# SCH_usbhubby_2024-08-02.net
KiCad netlist of a schematic drawn in EasyEDA
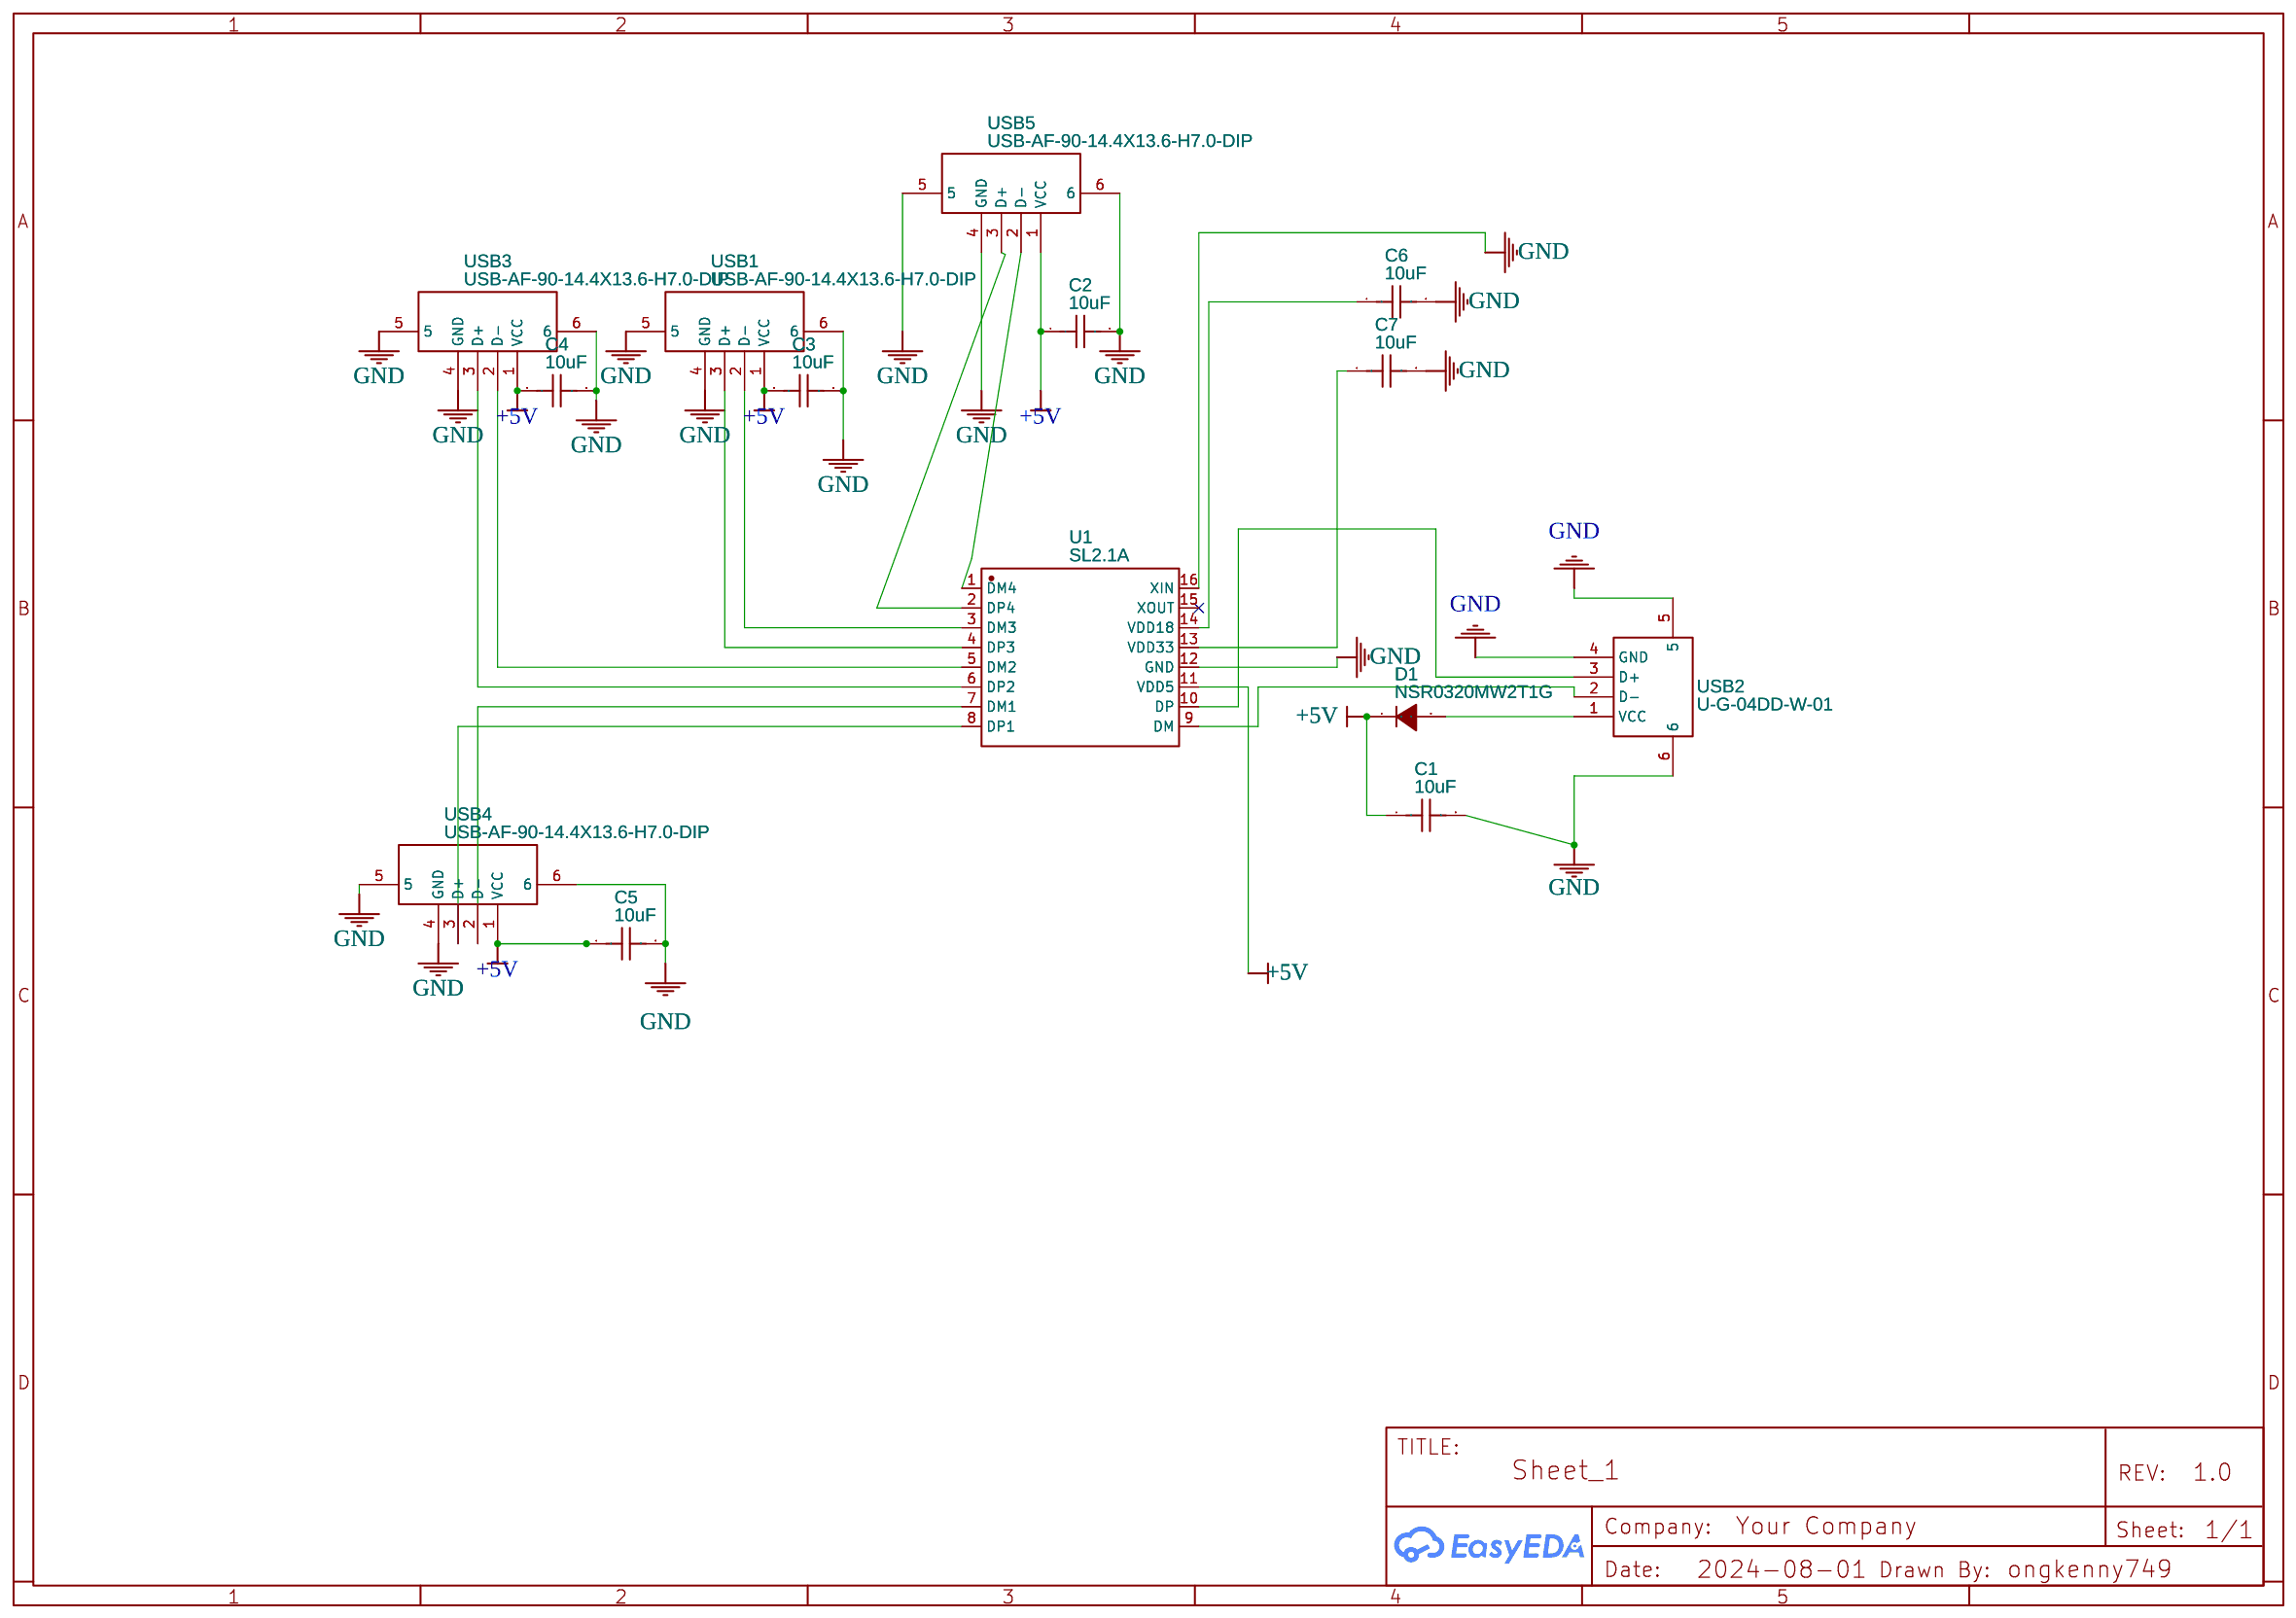
[diagram p0: schematic sheet]

(export (version "E")
  (design (tool "Eeschema 10.0.6"))
  (components
    (comp (ref "C1")
      (value "10uF")
      (fields
        (field (name "Manufacturer Part") "CL10A106KP8NNNC")
        (field (name "Manufacturer") "SAMSUNG(三星)")
      )
      (libsource (lib "") (part "CL10A106KP8NNNC"))
    )
    (comp (ref "C2")
      (value "10uF")
      (fields
        (field (name "Manufacturer Part") "CL10A106KP8NNNC")
        (field (name "Manufacturer") "SAMSUNG(三星)")
      )
      (libsource (lib "") (part "CL10A106KP8NNNC"))
    )
    (comp (ref "C3")
      (value "10uF")
      (fields
        (field (name "Manufacturer Part") "CL10A106KP8NNNC")
        (field (name "Manufacturer") "SAMSUNG(三星)")
      )
      (libsource (lib "") (part "CL10A106KP8NNNC"))
    )
    (comp (ref "C4")
      (value "10uF")
      (fields
        (field (name "Manufacturer Part") "CL10A106KP8NNNC")
        (field (name "Manufacturer") "SAMSUNG(三星)")
      )
      (libsource (lib "") (part "CL10A106KP8NNNC"))
    )
    (comp (ref "C5")
      (value "10uF")
      (fields
        (field (name "Manufacturer Part") "CL10A106KP8NNNC")
        (field (name "Manufacturer") "SAMSUNG(三星)")
      )
      (libsource (lib "") (part "CL10A106KP8NNNC"))
    )
    (comp (ref "C6")
      (value "10uF")
      (fields
        (field (name "Manufacturer Part") "CL10A106KP8NNNC")
        (field (name "Manufacturer") "SAMSUNG(三星)")
      )
      (libsource (lib "") (part "CL10A106KP8NNNC"))
    )
    (comp (ref "C7")
      (value "10uF")
      (fields
        (field (name "Manufacturer Part") "CL10A106KP8NNNC")
        (field (name "Manufacturer") "SAMSUNG(三星)")
      )
      (libsource (lib "") (part "CL10A106KP8NNNC"))
    )
    (comp (ref "D1")
      (value "NSR0320MW2T1G")
      (fields (field (name "Manufacturer") "onsemi(安森美)"))
      (libsource (lib "") (part "NSR0320MW2T1G"))
    )
    (comp (ref "U1")
      (value "SL2.1A")
      (fields (field (name "Manufacturer") "CoreChips(和芯润德)"))
      (libsource (lib "") (part "SL2.1A"))
    )
    (comp (ref "USB1")
      (value "USB-AF-90-14.4X13.6-H7.0-DIP")
      (fields (field (name "Manufacturer Part") "903-131A1011D10100") (field (name "Manufacturer") "精拓金"))
      (libsource (lib "") (part "USB-AF-90-14.4X13.6-H7.0-DIP"))
    )
    (comp (ref "USB2")
      (value "U-G-04DD-W-01")
      (fields (field (name "Manufacturer Part") "U-G-O4DD-W-1") (field (name "Manufacturer") "韩国韩荣"))
      (libsource (lib "") (part "U-G-04DD-W-01"))
    )
    (comp (ref "USB3")
      (value "USB-AF-90-14.4X13.6-H7.0-DIP")
      (fields (field (name "Manufacturer Part") "903-131A1011D10100") (field (name "Manufacturer") "精拓金"))
      (libsource (lib "") (part "USB-AF-90-14.4X13.6-H7.0-DIP"))
    )
    (comp (ref "USB4")
      (value "USB-AF-90-14.4X13.6-H7.0-DIP")
      (fields (field (name "Manufacturer Part") "903-131A1011D10100") (field (name "Manufacturer") "精拓金"))
      (libsource (lib "") (part "USB-AF-90-14.4X13.6-H7.0-DIP"))
    )
    (comp (ref "USB5")
      (value "USB-AF-90-14.4X13.6-H7.0-DIP")
      (fields (field (name "Manufacturer Part") "903-131A1011D10100") (field (name "Manufacturer") "精拓金"))
      (libsource (lib "") (part "USB-AF-90-14.4X13.6-H7.0-DIP"))
    )
  )
  (nets
    (net (code "1") (name "+5V") (class "Default")
      (node (ref "C1") (pin "1") (pinfunction "1_1") (pintype "unspecified"))
      (node (ref "C2") (pin "1") (pinfunction "1_1") (pintype "unspecified"))
      (node (ref "C3") (pin "1") (pinfunction "1_1") (pintype "unspecified"))
      (node (ref "C4") (pin "1") (pinfunction "1_1") (pintype "unspecified"))
      (node (ref "C5") (pin "1") (pinfunction "1_1") (pintype "unspecified"))
      (node (ref "D1") (pin "1") (pinfunction "C_1") (pintype "unspecified"))
      (node (ref "U1") (pin "11") (pinfunction "VDD5_11") (pintype "unspecified"))
      (node (ref "USB1") (pin "1") (pinfunction "VCC_1") (pintype "unspecified"))
      (node (ref "USB3") (pin "1") (pinfunction "VCC_1") (pintype "unspecified"))
      (node (ref "USB4") (pin "1") (pinfunction "VCC_1") (pintype "unspecified"))
      (node (ref "USB5") (pin "1") (pinfunction "VCC_1") (pintype "unspecified"))
    )
    (net (code "2") (name "GND") (class "Default")
      (node (ref "C1") (pin "2") (pinfunction "2_2") (pintype "unspecified"))
      (node (ref "C2") (pin "2") (pinfunction "2_2") (pintype "unspecified"))
      (node (ref "C3") (pin "2") (pinfunction "2_2") (pintype "unspecified"))
      (node (ref "C4") (pin "2") (pinfunction "2_2") (pintype "unspecified"))
      (node (ref "C5") (pin "2") (pinfunction "2_2") (pintype "unspecified"))
      (node (ref "C6") (pin "2") (pinfunction "2_2") (pintype "unspecified"))
      (node (ref "C7") (pin "2") (pinfunction "2_2") (pintype "unspecified"))
      (node (ref "U1") (pin "12") (pinfunction "GND_12") (pintype "unspecified"))
      (node (ref "U1") (pin "16") (pinfunction "XIN_16") (pintype "unspecified"))
      (node (ref "USB1") (pin "4") (pinfunction "GND_4") (pintype "unspecified"))
      (node (ref "USB1") (pin "5") (pinfunction "5_5") (pintype "unspecified"))
      (node (ref "USB1") (pin "6") (pinfunction "6_6") (pintype "unspecified"))
      (node (ref "USB2") (pin "4") (pinfunction "GND_4") (pintype "unspecified"))
      (node (ref "USB2") (pin "5") (pinfunction "5_5") (pintype "unspecified"))
      (node (ref "USB2") (pin "6") (pinfunction "6_6") (pintype "unspecified"))
      (node (ref "USB3") (pin "4") (pinfunction "GND_4") (pintype "unspecified"))
      (node (ref "USB3") (pin "5") (pinfunction "5_5") (pintype "unspecified"))
      (node (ref "USB3") (pin "6") (pinfunction "6_6") (pintype "unspecified"))
      (node (ref "USB4") (pin "4") (pinfunction "GND_4") (pintype "unspecified"))
      (node (ref "USB4") (pin "5") (pinfunction "5_5") (pintype "unspecified"))
      (node (ref "USB4") (pin "6") (pinfunction "6_6") (pintype "unspecified"))
      (node (ref "USB5") (pin "4") (pinfunction "GND_4") (pintype "unspecified"))
      (node (ref "USB5") (pin "5") (pinfunction "5_5") (pintype "unspecified"))
      (node (ref "USB5") (pin "6") (pinfunction "6_6") (pintype "unspecified"))
    )
    (net (code "3") (name "Net-(D1-A)") (class "Default")
      (node (ref "D1") (pin "2") (pinfunction "A_2") (pintype "unspecified"))
      (node (ref "USB2") (pin "1") (pinfunction "VCC_1") (pintype "unspecified"))
    )
    (net (code "4") (name "Net-(U1-DM)") (class "Default")
      (node (ref "U1") (pin "9") (pinfunction "DM_9") (pintype "unspecified"))
      (node (ref "USB2") (pin "2") (pinfunction "D-_2") (pintype "unspecified"))
    )
    (net (code "5") (name "Net-(U1-DM1)") (class "Default")
      (node (ref "U1") (pin "7") (pinfunction "DM1_7") (pintype "unspecified"))
      (node (ref "USB4") (pin "2") (pinfunction "D-_2") (pintype "unspecified"))
    )
    (net (code "6") (name "Net-(U1-DM2)") (class "Default")
      (node (ref "U1") (pin "5") (pinfunction "DM2_5") (pintype "unspecified"))
      (node (ref "USB3") (pin "2") (pinfunction "D-_2") (pintype "unspecified"))
    )
    (net (code "7") (name "Net-(U1-DM3)") (class "Default")
      (node (ref "U1") (pin "3") (pinfunction "DM3_3") (pintype "unspecified"))
      (node (ref "USB1") (pin "2") (pinfunction "D-_2") (pintype "unspecified"))
    )
    (net (code "8") (name "Net-(U1-DM4)") (class "Default")
      (node (ref "U1") (pin "1") (pinfunction "DM4_1") (pintype "unspecified"))
      (node (ref "USB5") (pin "2") (pinfunction "D-_2") (pintype "unspecified"))
    )
    (net (code "9") (name "Net-(U1-DP)") (class "Default")
      (node (ref "U1") (pin "10") (pinfunction "DP_10") (pintype "unspecified"))
      (node (ref "USB2") (pin "3") (pinfunction "D+_3") (pintype "unspecified"))
    )
    (net (code "10") (name "Net-(U1-DP1)") (class "Default")
      (node (ref "U1") (pin "8") (pinfunction "DP1_8") (pintype "unspecified"))
      (node (ref "USB4") (pin "3") (pinfunction "D+_3") (pintype "unspecified"))
    )
    (net (code "11") (name "Net-(U1-DP2)") (class "Default")
      (node (ref "U1") (pin "6") (pinfunction "DP2_6") (pintype "unspecified"))
      (node (ref "USB3") (pin "3") (pinfunction "D+_3") (pintype "unspecified"))
    )
    (net (code "12") (name "Net-(U1-DP3)") (class "Default")
      (node (ref "U1") (pin "4") (pinfunction "DP3_4") (pintype "unspecified"))
      (node (ref "USB1") (pin "3") (pinfunction "D+_3") (pintype "unspecified"))
    )
    (net (code "13") (name "Net-(U1-DP4)") (class "Default")
      (node (ref "U1") (pin "2") (pinfunction "DP4_2") (pintype "unspecified"))
      (node (ref "USB5") (pin "3") (pinfunction "D+_3") (pintype "unspecified"))
    )
    (net (code "14") (name "Net-(U1-VDD18)") (class "Default")
      (node (ref "C6") (pin "1") (pinfunction "1_1") (pintype "unspecified"))
      (node (ref "U1") (pin "14") (pinfunction "VDD18_14") (pintype "unspecified"))
    )
    (net (code "15") (name "Net-(U1-VDD33)") (class "Default")
      (node (ref "C7") (pin "1") (pinfunction "1_1") (pintype "unspecified"))
      (node (ref "U1") (pin "13") (pinfunction "VDD33_13") (pintype "unspecified"))
    )
    (net (code "16") (name "unconnected-(U1-XOUT-Pad15)") (class "Default")
      (node (ref "U1") (pin "15") (pinfunction "XOUT_15") (pintype "unspecified+no_connect"))
    )
  )
)
